# voltage_regulation.net
KiCad netlist of a schematic drawn in Altium Designer
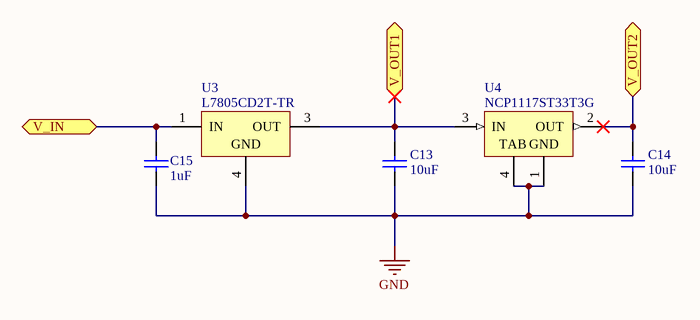
[diagram p0: voltage_regulation.SchDoc]

(export (version "E")
  (design (tool "Eeschema 10.0.6"))
  (components
    (comp (ref "C13")
      (value "10uF")
      (footprint "C2012")
      (description "Capacitor")
      (fields
        (field (name "MANUFACTURER") "MULTICOMP")
        (field (name "MANUFACTURER PART NUMBER") "MC0805X106K250CT")
        (field (name "PUBLISHER") "Altium Limited")
      )
      (libsource (lib "Miscellaneous Devices") (part "Cap"))
    )
    (comp (ref "C14")
      (value "10uF")
      (footprint "C2012")
      (description "Capacitor")
      (fields
        (field (name "MANUFACTURER") "MULTICOMP")
        (field (name "MANUFACTURER PART NUMBER") "MC0805X106K250CT")
        (field (name "PUBLISHER") "Altium Limited")
      )
      (libsource (lib "Miscellaneous Devices") (part "Cap"))
    )
    (comp (ref "C15")
      (value "1uF")
      (footprint "C2012")
      (description "Capacitor")
      (fields
        (field (name "MANUFACTURER") "MULTICOMP")
        (field (name "MANUFACTURER PART NUMBER") "MC0805B105K250CT")
        (field (name "PUBLISHER") "Altium Limited")
      )
      (libsource (lib "Miscellaneous Devices") (part "Cap"))
    )
    (comp (ref "U3")
      (value "L7805CD2T-TR")
      (footprint "TO-263_M")
      (description "Positive Voltage Regulator, 3-Pin D2PAK, Tape and Reel")
      (libsource (lib "Altium Content Vault") (part "CMP-0244-00213-1"))
    )
    (comp (ref "U4")
      (value "NCP1117ST33T3G")
      (footprint "ONSC-SOT-223_L")
      (fields (field (name "PARTNUMBER") "NCP1117ST50T3G") (field (name "MANUFACTURER") "ON Semiconductor"))
      (libsource (lib "Altium Content Vault") (part "CMP-0592-00001-2"))
    )
  )
  (nets
    (net (code "1") (name "/V_IN") (class "Default")
      (node (ref "C15") (pin "1") (pinfunction "1_1") (pintype "passive"))
      (node (ref "U3") (pin "1") (pinfunction "IN_1") (pintype "power_in"))
    )
    (net (code "2") (name "/V_OUT1") (class "Default")
      (node (ref "C13") (pin "2") (pinfunction "2_2") (pintype "passive"))
      (node (ref "U3") (pin "3") (pinfunction "OUT_3") (pintype "power_in"))
      (node (ref "U4") (pin "3") (pinfunction "IN_3") (pintype "input"))
    )
    (net (code "3") (name "/V_OUT2") (class "Default")
      (node (ref "C14") (pin "2") (pinfunction "2_2") (pintype "passive"))
      (node (ref "U4") (pin "2") (pinfunction "OUT_2") (pintype "output"))
    )
    (net (code "4") (name "GND") (class "Default")
      (node (ref "C13") (pin "1") (pinfunction "1_1") (pintype "passive"))
      (node (ref "C14") (pin "1") (pinfunction "1_1") (pintype "passive"))
      (node (ref "C15") (pin "2") (pinfunction "2_2") (pintype "passive"))
      (node (ref "U3") (pin "4") (pinfunction "GND_4") (pintype "power_in"))
      (node (ref "U4") (pin "1") (pinfunction "GND_1") (pintype "power_in"))
      (node (ref "U4") (pin "4") (pinfunction "TAB_4") (pintype "power_in"))
    )
  )
)
